# np001.net
KiCad netlist of a schematic drawn in Altium Designer
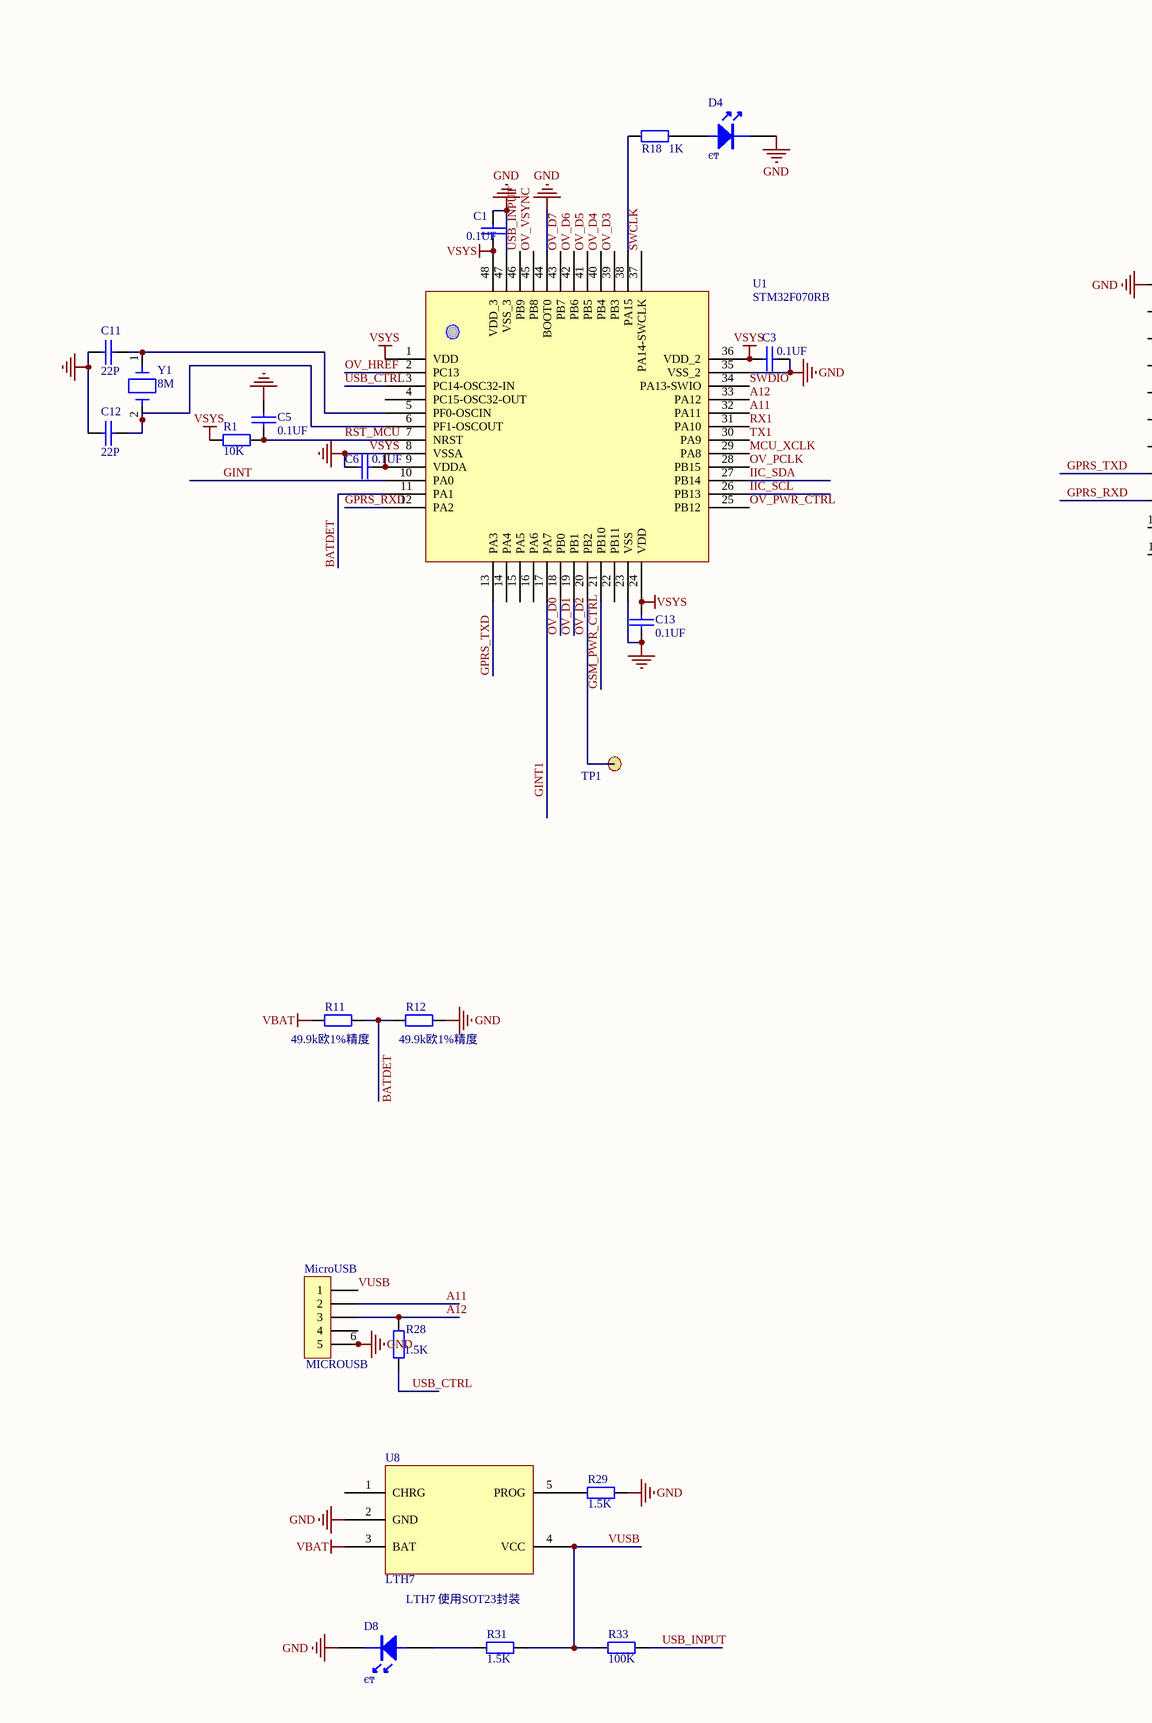
[diagram p0: np001.schdoc, left]
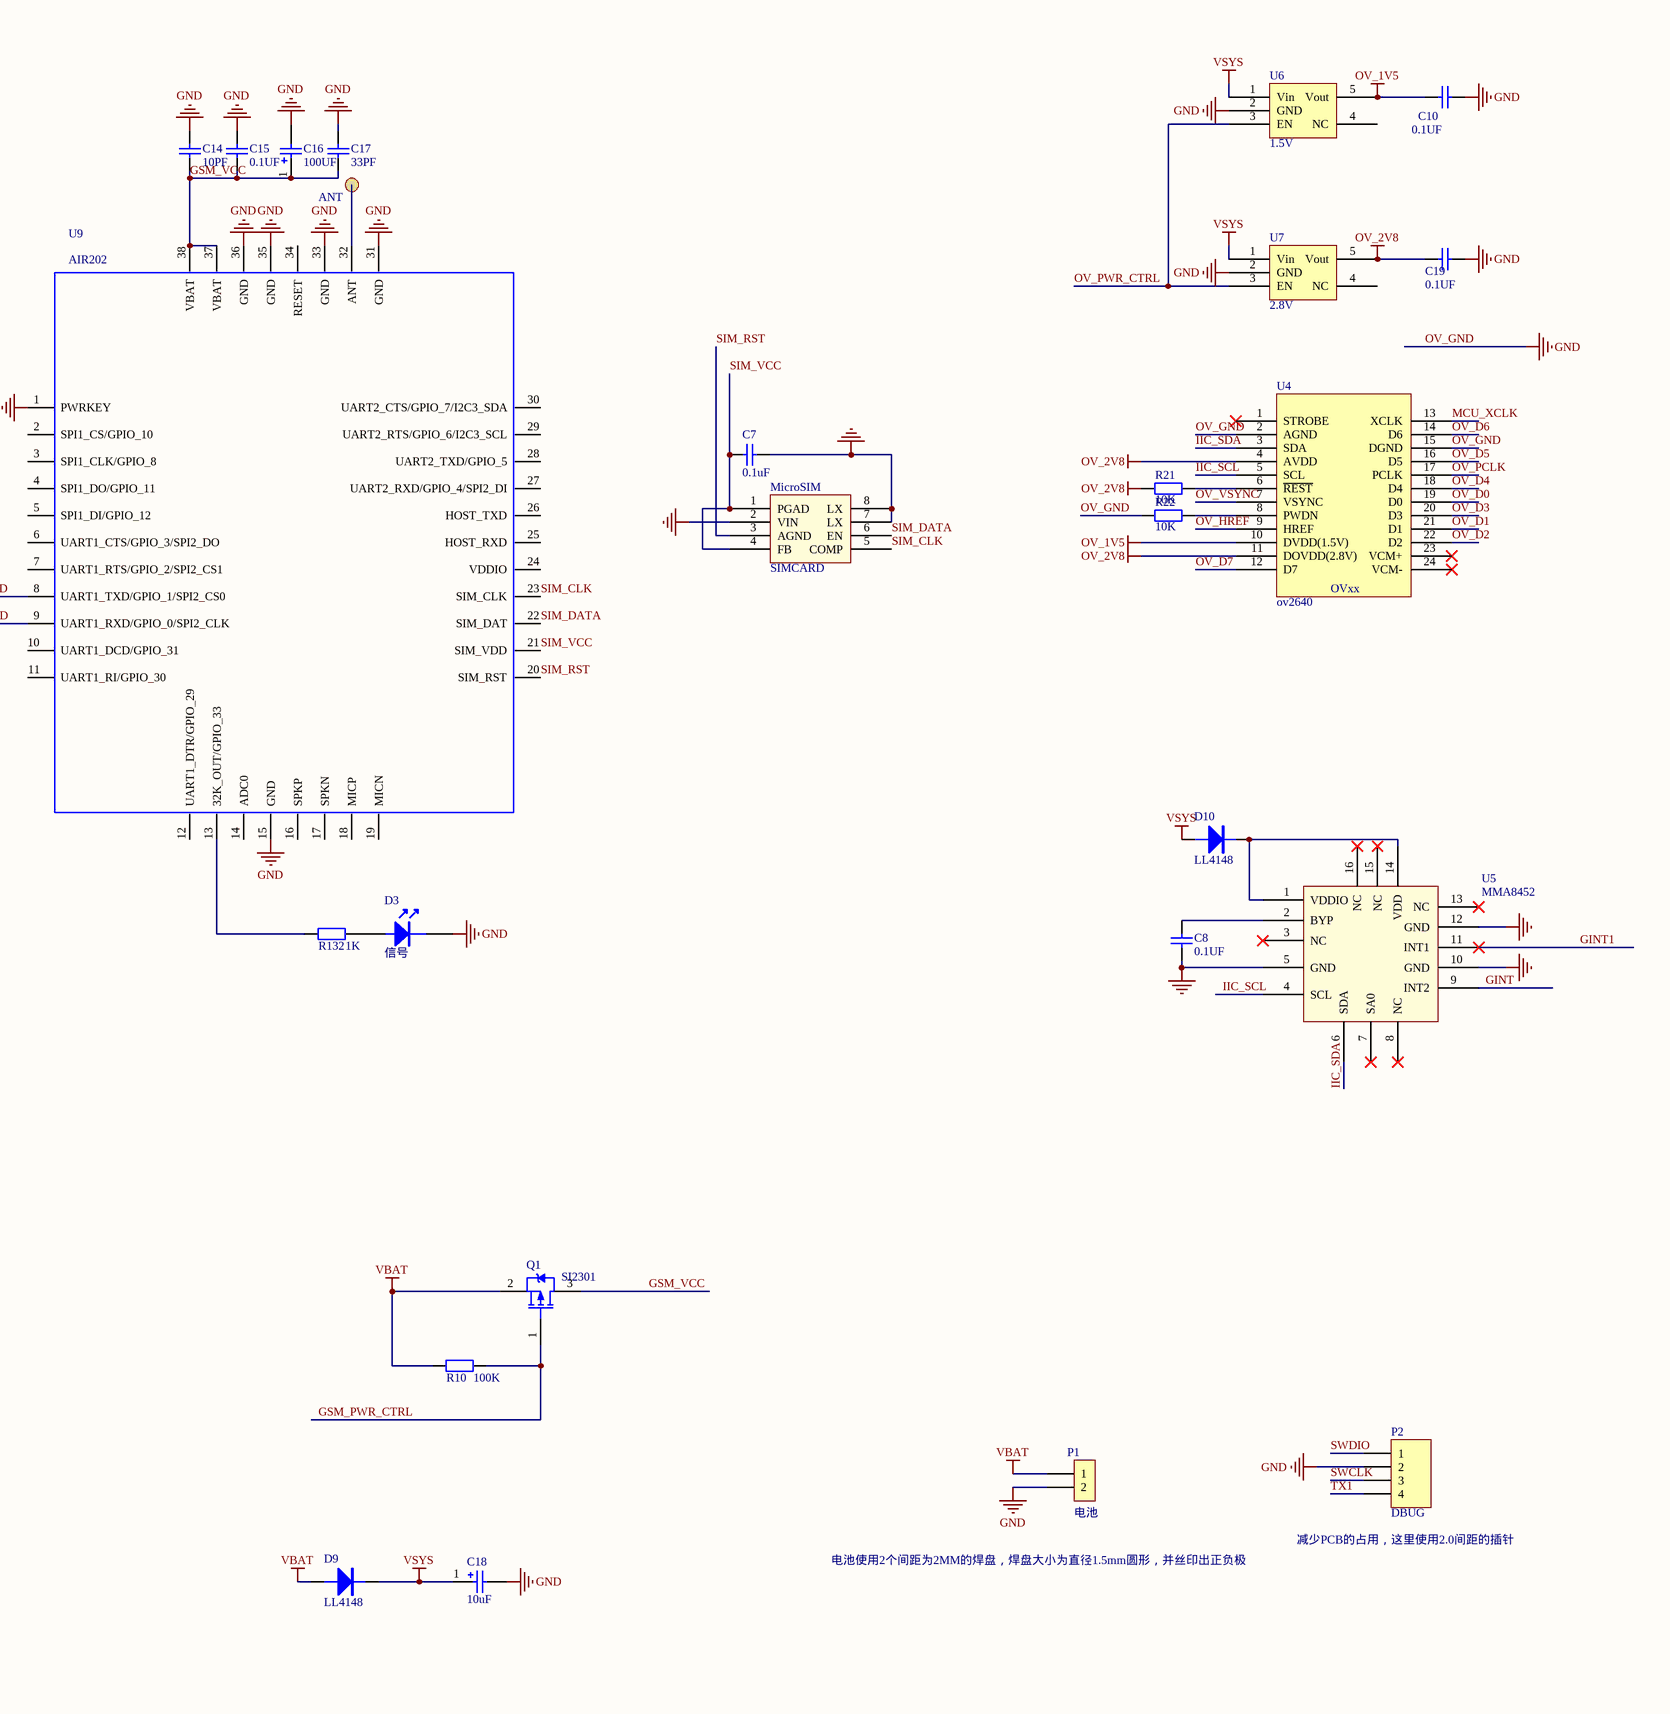
[diagram p1: np001.schdoc, right]

(export (version "E")
  (design (tool "Eeschema 10.0.6"))
  (components
    (comp (ref "ANT") (value "TP") (footprint "CON1") (libsource (lib "HARRIG_Schlib") (part "TP")))
    (comp (ref "C1")
      (value "0.1UF")
      (footprint "0603")
      (description "Capacitor")
      (libsource (lib "*") (part "CAP"))
    )
    (comp (ref "C3")
      (value "0.1UF")
      (footprint "0603")
      (description "Capacitor")
      (libsource (lib "*") (part "CAP"))
    )
    (comp (ref "C5")
      (value "0.1UF")
      (footprint "0603")
      (description "Capacitor")
      (libsource (lib "*") (part "CAP"))
    )
    (comp (ref "C6")
      (value "0.1UF")
      (footprint "0603")
      (description "Capacitor")
      (libsource (lib "*") (part "CAP"))
    )
    (comp (ref "C7")
      (value "0.1uF")
      (footprint "C0603")
      (description "Capacitor")
      (fields (field (name "PUBLISHER") "Altium Limited"))
      (libsource (lib "Miscellaneous Devices") (part "Cap"))
    )
    (comp (ref "C8") (value "0.1UF") (footprint "0603") (libsource (lib "My lib") (part "Cap")))
    (comp (ref "C10") (value "0.1UF") (footprint "0603") (libsource (lib "我的集成库") (part "CAP")))
    (comp (ref "C11")
      (value "22P")
      (footprint "0603")
      (description "Capacitor")
      (libsource (lib "*") (part "CAP"))
    )
    (comp (ref "C12")
      (value "22P")
      (footprint "0603")
      (description "Capacitor")
      (libsource (lib "*") (part "CAP"))
    )
    (comp (ref "C13")
      (value "0.1UF")
      (footprint "0603")
      (description "Capacitor")
      (libsource (lib "*") (part "CAP"))
    )
    (comp (ref "C14") (value "10PF") (footprint "0603") (libsource (lib "我的集成库") (part "CAP")))
    (comp (ref "C15") (value "0.1UF") (footprint "0603") (libsource (lib "我的集成库") (part "CAP")))
    (comp (ref "C16") (value "100UF") (footprint "C7343") (libsource (lib "My lib") (part "Cap_+")))
    (comp (ref "C17") (value "33PF") (footprint "0603") (libsource (lib "我的集成库") (part "CAP")))
    (comp (ref "C18") (value "10uF") (footprint "C3216_10V") (libsource (lib "My lib") (part "Cap_+")))
    (comp (ref "C19") (value "0.1UF") (footprint "0603") (libsource (lib "我的集成库") (part "CAP")))
    (comp (ref "D3") (value "信号") (footprint "LED0603") (libsource (lib "TC35_1") (part "LED")))
    (comp (ref "D4") (value "系统") (footprint "LED0603") (libsource (lib "TC35_1") (part "LED")))
    (comp (ref "D8") (value "系统") (footprint "LED0603") (libsource (lib "TC35_1") (part "LED")))
    (comp (ref "D9") (value "LL4148") (footprint "D1206") (libsource (lib "HZ_LIB") (part "DIODE")))
    (comp (ref "D10") (value "LL4148") (footprint "D1206") (libsource (lib "HZ_LIB") (part "DIODE")))
    (comp (ref "MicroSIM")
      (value "SIMCARD")
      (footprint "PCBComponent_1 - duplicate1")
      (libsource (lib "ARM-ESP8266") (part "aoz1073"))
    )
    (comp (ref "MicroUSB")
      (value "MICROUSB")
      (footprint "mircousb")
      (description "Connector")
      (libsource (lib "sch") (part "CON5"))
    )
    (comp (ref "P1") (value "电池") (footprint "HDR1X2") (libsource (lib "My lib") (part "Header_2")))
    (comp (ref "P2")
      (value "DBUG")
      (footprint "HDR1X4-2.0B")
      (description "Header, 4-Pin, Right Angle")
      (fields (field (name "PUBLISHER") "Altium Limited"))
      (libsource (lib "Miscellaneous Connectors") (part "Header 4H"))
    )
    (comp (ref "Q1")
      (value "SI2301")
      (footprint "SOT-23")
      (description "P-Channel Power MOSFET")
      (fields (field (name "PUBLISHER") "Altium Limited"))
      (libsource (lib "Miscellaneous Devices") (part "PMOS-2"))
    )
    (comp (ref "R1")
      (value "10K")
      (footprint "0603")
      (description "Resistor")
      (fields (field (name "PUBLISHER") "*"))
      (libsource (lib "TC35_1") (part "Res2"))
    )
    (comp (ref "R10")
      (value "100K")
      (footprint "0603")
      (description "Resistor")
      (fields (field (name "PUBLISHER") "*"))
      (libsource (lib "TC35_1") (part "Res2"))
    )
    (comp (ref "R11")
      (value "49.9k欧1%精度")
      (footprint "0603")
      (description "Resistor")
      (fields (field (name "PUBLISHER") "*"))
      (libsource (lib "TC35_1") (part "Res2"))
    )
    (comp (ref "R12")
      (value "49.9k欧1%精度")
      (footprint "0603")
      (description "Resistor")
      (fields (field (name "PUBLISHER") "*"))
      (libsource (lib "TC35_1") (part "Res2"))
    )
    (comp (ref "R18")
      (value "1K")
      (footprint "0603")
      (description "Resistor")
      (fields (field (name "PUBLISHER") "*"))
      (libsource (lib "TC35_1") (part "Res2"))
    )
    (comp (ref "R21")
      (value "10K")
      (footprint "0603")
      (description "Resistor")
      (fields (field (name "PUBLISHER") "*"))
      (libsource (lib "") (part "Res2_1"))
    )
    (comp (ref "R22")
      (value "10K")
      (footprint "0603")
      (description "Resistor")
      (fields (field (name "PUBLISHER") "*"))
      (libsource (lib "") (part "Res2_1"))
    )
    (comp (ref "R28") (value "1.5K") (footprint "0603") (libsource (lib "My lib") (part "Res_SMT")))
    (comp (ref "R29") (value "1.5K") (footprint "0603") (libsource (lib "") (part "Res_SMT_1")))
    (comp (ref "R31") (value "1.5K") (footprint "0603") (libsource (lib "") (part "Res_SMT_2")))
    (comp (ref "R33")
      (value "100K")
      (footprint "0603")
      (description "Resistor")
      (fields (field (name "PUBLISHER") "*"))
      (libsource (lib "TC35_1") (part "Res2"))
    )
    (comp (ref "R132")
      (value "1K")
      (footprint "0603")
      (description "Resistor")
      (fields (field (name "PUBLISHER") "*"))
      (libsource (lib "TC35_1") (part "Res2"))
    )
    (comp (ref "TP1") (value "TP") (footprint "CON1") (libsource (lib "HARRIG_Schlib") (part "TP")))
    (comp (ref "U1") (value "STM32F070RB") (footprint "LQFP48") (libsource (lib "xn") (part "STM32070RB")))
    (comp (ref "U4") (value "ov2640") (footprint "OV2640") (libsource (lib "xn") (part "ov2640")))
    (comp (ref "U5") (value "MMA8452") (footprint "LCC16") (libsource (lib "My lib") (part "MMA8452")))
    (comp (ref "U6") (value "1.5V") (footprint "SOT753") (libsource (lib "我的集成库") (part "NCP699_LDO")))
    (comp (ref "U7") (value "2.8V") (footprint "SOT753") (libsource (lib "我的集成库") (part "NCP699_LDO")))
    (comp (ref "U8") (value "LTH7") (footprint "SOT-23-5") (libsource (lib "air200") (part "LTH7")))
    (comp (ref "U9") (value "AIR202") (footprint "A6391_A11") (libsource (lib "Air202") (part "A6391_A11")))
    (comp (ref "Y1") (value "8M") (footprint "CRY_5032_2P") (libsource (lib "*") (part "CRYTAL")))
  )
  (nets
    (net (code "1") (name "/A11") (class "Default")
      (node (ref "MicroUSB") (pin "2") (pinfunction "2_2") (pintype "passive"))
      (node (ref "U1") (pin "32") (pinfunction "PA11_32") (pintype "passive"))
    )
    (net (code "2") (name "/A12") (class "Default")
      (node (ref "MicroUSB") (pin "3") (pinfunction "3_3") (pintype "passive"))
      (node (ref "R28") (pin "1") (pinfunction "1_1") (pintype "passive"))
      (node (ref "U1") (pin "33") (pinfunction "PA12_33") (pintype "passive"))
    )
    (net (code "3") (name "/BATDET") (class "Default")
      (node (ref "R11") (pin "2") (pinfunction "2_2") (pintype "passive"))
      (node (ref "R12") (pin "1") (pinfunction "1_1") (pintype "passive"))
      (node (ref "U1") (pin "11") (pinfunction "PA1_11") (pintype "passive"))
    )
    (net (code "4") (name "/GINT") (class "Default")
      (node (ref "U1") (pin "10") (pinfunction "PA0_10") (pintype "passive"))
      (node (ref "U5") (pin "9") (pinfunction "INT2_9") (pintype "passive"))
    )
    (net (code "5") (name "/GINT1") (class "Default")
      (node (ref "U1") (pin "17") (pinfunction "PA7_17") (pintype "passive"))
      (node (ref "U5") (pin "11") (pinfunction "INT1_11") (pintype "passive"))
    )
    (net (code "6") (name "/GPRS_RXD") (class "Default")
      (node (ref "U1") (pin "12") (pinfunction "PA2_12") (pintype "passive"))
      (node (ref "U9") (pin "9") (pinfunction "UART1_RXD/GPIO_0/SPI2_CLK_9") (pintype "passive"))
    )
    (net (code "7") (name "/GPRS_TXD") (class "Default")
      (node (ref "U1") (pin "13") (pinfunction "PA3_13") (pintype "passive"))
      (node (ref "U9") (pin "8") (pinfunction "UART1_TXD/GPIO_1/SPI2_CS0_8") (pintype "passive"))
    )
    (net (code "8") (name "/GSM_PWR_CTRL") (class "Default")
      (node (ref "Q1") (pin "1") (pinfunction "G_1") (pintype "passive"))
      (node (ref "R10") (pin "2") (pinfunction "2_2") (pintype "passive"))
      (node (ref "U1") (pin "21") (pinfunction "PB10_21") (pintype "passive"))
    )
    (net (code "9") (name "/GSM_VCC") (class "Default")
      (node (ref "C14") (pin "1") (pinfunction "1_1") (pintype "passive"))
      (node (ref "C15") (pin "1") (pinfunction "1_1") (pintype "passive"))
      (node (ref "C16") (pin "1") (pinfunction "P_1") (pintype "passive"))
      (node (ref "C17") (pin "1") (pinfunction "1_1") (pintype "passive"))
      (node (ref "Q1") (pin "3") (pinfunction "D_3") (pintype "passive"))
      (node (ref "U9") (pin "37") (pinfunction "VBAT_37") (pintype "passive"))
      (node (ref "U9") (pin "38") (pinfunction "VBAT_38") (pintype "passive"))
    )
    (net (code "10") (name "/IIC_SCL") (class "Default")
      (node (ref "U1") (pin "26") (pinfunction "PB13_26") (pintype "passive"))
      (node (ref "U4") (pin "5") (pinfunction "SCL_5") (pintype "passive"))
      (node (ref "U5") (pin "4") (pinfunction "SCL_4") (pintype "passive"))
    )
    (net (code "11") (name "/IIC_SDA") (class "Default")
      (node (ref "U1") (pin "27") (pinfunction "PB14_27") (pintype "passive"))
      (node (ref "U4") (pin "3") (pinfunction "SDA_3") (pintype "passive"))
      (node (ref "U5") (pin "6") (pinfunction "SDA_6") (pintype "passive"))
    )
    (net (code "12") (name "/MCU_XCLK") (class "Default")
      (node (ref "U1") (pin "29") (pinfunction "PA8_29") (pintype "passive"))
      (node (ref "U4") (pin "13") (pinfunction "XCLK_13") (pintype "passive"))
    )
    (net (code "13") (name "/OV_D0") (class "Default")
      (node (ref "U1") (pin "18") (pinfunction "PB0_18") (pintype "passive"))
      (node (ref "U4") (pin "19") (pinfunction "D0_19") (pintype "passive"))
    )
    (net (code "14") (name "/OV_D1") (class "Default")
      (node (ref "U1") (pin "19") (pinfunction "PB1_19") (pintype "passive"))
      (node (ref "U4") (pin "21") (pinfunction "D1_21") (pintype "passive"))
    )
    (net (code "15") (name "/OV_D2") (class "Default")
      (node (ref "TP1") (pin "1") (pintype "passive"))
      (node (ref "U1") (pin "20") (pinfunction "PB2_20") (pintype "passive"))
      (node (ref "U4") (pin "22") (pinfunction "D2_22") (pintype "passive"))
    )
    (net (code "16") (name "/OV_D3") (class "Default")
      (node (ref "U1") (pin "39") (pinfunction "PB3_39") (pintype "passive"))
      (node (ref "U4") (pin "20") (pinfunction "D3_20") (pintype "passive"))
    )
    (net (code "17") (name "/OV_D4") (class "Default")
      (node (ref "U1") (pin "40") (pinfunction "PB4_40") (pintype "passive"))
      (node (ref "U4") (pin "18") (pinfunction "D4_18") (pintype "passive"))
    )
    (net (code "18") (name "/OV_D5") (class "Default")
      (node (ref "U1") (pin "41") (pinfunction "PB5_41") (pintype "passive"))
      (node (ref "U4") (pin "16") (pinfunction "D5_16") (pintype "passive"))
    )
    (net (code "19") (name "/OV_D6") (class "Default")
      (node (ref "U1") (pin "42") (pinfunction "PB6_42") (pintype "passive"))
      (node (ref "U4") (pin "14") (pinfunction "D6_14") (pintype "passive"))
    )
    (net (code "20") (name "/OV_D7") (class "Default")
      (node (ref "U1") (pin "43") (pinfunction "PB7_43") (pintype "passive"))
      (node (ref "U4") (pin "12") (pinfunction "D7_12") (pintype "passive"))
    )
    (net (code "21") (name "/OV_HREF") (class "Default")
      (node (ref "U1") (pin "2") (pinfunction "PC13_2") (pintype "passive"))
      (node (ref "U4") (pin "9") (pinfunction "HREF_9") (pintype "passive"))
    )
    (net (code "22") (name "/OV_PCLK") (class "Default")
      (node (ref "U1") (pin "28") (pinfunction "PB15_28") (pintype "passive"))
      (node (ref "U4") (pin "17") (pinfunction "PCLK_17") (pintype "passive"))
    )
    (net (code "23") (name "/OV_PWR_CTRL") (class "Default")
      (node (ref "U1") (pin "25") (pinfunction "PB12_25") (pintype "passive"))
      (node (ref "U6") (pin "3") (pinfunction "EN_3") (pintype "passive"))
      (node (ref "U7") (pin "3") (pinfunction "EN_3") (pintype "passive"))
    )
    (net (code "24") (name "/OV_VSYNC") (class "Default")
      (node (ref "U1") (pin "45") (pinfunction "PB8_45") (pintype "passive"))
      (node (ref "U4") (pin "7") (pinfunction "VSYNC_7") (pintype "passive"))
    )
    (net (code "25") (name "/RST_MCU") (class "Default")
      (node (ref "C5") (pin "1") (pinfunction "1_1") (pintype "passive"))
      (node (ref "R1") (pin "2") (pinfunction "2_2") (pintype "passive"))
      (node (ref "U1") (pin "7") (pinfunction "NRST_7") (pintype "passive"))
    )
    (net (code "26") (name "/RX1") (class "Default")
      (node (ref "U1") (pin "31") (pinfunction "PA10_31") (pintype "passive"))
    )
    (net (code "27") (name "/SIM_CLK") (class "Default")
      (node (ref "MicroSIM") (pin "5") (pinfunction "COMP_5") (pintype "passive"))
      (node (ref "U9") (pin "23") (pinfunction "SIM_CLK_23") (pintype "passive"))
    )
    (net (code "28") (name "/SIM_DATA") (class "Default")
      (node (ref "MicroSIM") (pin "6") (pinfunction "EN_6") (pintype "passive"))
      (node (ref "U9") (pin "22") (pinfunction "SIM_DAT_22") (pintype "passive"))
    )
    (net (code "29") (name "/SIM_RST") (class "Default")
      (node (ref "MicroSIM") (pin "3") (pinfunction "AGND_3") (pintype "passive"))
      (node (ref "U9") (pin "20") (pinfunction "SIM_RST_20") (pintype "passive"))
    )
    (net (code "30") (name "/SIM_VCC") (class "Default")
      (node (ref "C7") (pin "1") (pinfunction "1_1") (pintype "passive"))
      (node (ref "MicroSIM") (pin "1") (pinfunction "PGAD_1") (pintype "passive"))
      (node (ref "MicroSIM") (pin "4") (pinfunction "FB_4") (pintype "passive"))
      (node (ref "U9") (pin "21") (pinfunction "SIM_VDD_21") (pintype "passive"))
    )
    (net (code "31") (name "/SWCLK") (class "Default")
      (node (ref "P2") (pin "3") (pinfunction "3_3") (pintype "passive"))
      (node (ref "U1") (pin "37") (pinfunction "PA14-SWCLK_37") (pintype "passive"))
    )
    (net (code "32") (name "/SWDIO") (class "Default")
      (node (ref "P2") (pin "1") (pinfunction "1_1") (pintype "passive"))
      (node (ref "U1") (pin "34") (pinfunction "PA13-SWIO_34") (pintype "passive"))
    )
    (net (code "33") (name "/TX1") (class "Default")
      (node (ref "P2") (pin "4") (pinfunction "4_4") (pintype "passive"))
      (node (ref "U1") (pin "30") (pinfunction "PA9_30") (pintype "passive"))
    )
    (net (code "34") (name "/USB_CTRL") (class "Default")
      (node (ref "R28") (pin "2") (pinfunction "2_2") (pintype "passive"))
      (node (ref "U1") (pin "3") (pinfunction "PC14-OSC32-IN_3") (pintype "passive"))
    )
    (net (code "35") (name "/USB_INPUT") (class "Default")
      (node (ref "R33") (pin "2") (pinfunction "2_2") (pintype "passive"))
      (node (ref "U1") (pin "46") (pinfunction "PB9_46") (pintype "passive"))
    )
    (net (code "36") (name "/VUSB") (class "Default")
      (node (ref "MicroUSB") (pin "1") (pinfunction "1_1") (pintype "passive"))
      (node (ref "R31") (pin "1") (pinfunction "1_1") (pintype "passive"))
      (node (ref "R33") (pin "1") (pinfunction "1_1") (pintype "passive"))
      (node (ref "U8") (pin "4") (pinfunction "VCC_4") (pintype "passive"))
    )
    (net (code "37") (name "GND") (class "Default")
      (node (ref "C1") (pin "2") (pinfunction "2_2") (pintype "passive"))
      (node (ref "C10") (pin "2") (pinfunction "2_2") (pintype "passive"))
      (node (ref "C11") (pin "2") (pinfunction "2_2") (pintype "passive"))
      (node (ref "C12") (pin "2") (pinfunction "2_2") (pintype "passive"))
      (node (ref "C13") (pin "2") (pinfunction "2_2") (pintype "passive"))
      (node (ref "C14") (pin "2") (pinfunction "2_2") (pintype "passive"))
      (node (ref "C15") (pin "2") (pinfunction "2_2") (pintype "passive"))
      (node (ref "C16") (pin "2") (pinfunction "N_2") (pintype "passive"))
      (node (ref "C17") (pin "2") (pinfunction "2_2") (pintype "passive"))
      (node (ref "C18") (pin "2") (pinfunction "N_2") (pintype "passive"))
      (node (ref "C19") (pin "2") (pinfunction "2_2") (pintype "passive"))
      (node (ref "C3") (pin "2") (pinfunction "2_2") (pintype "passive"))
      (node (ref "C5") (pin "2") (pinfunction "2_2") (pintype "passive"))
      (node (ref "C6") (pin "1") (pinfunction "1_1") (pintype "passive"))
      (node (ref "C7") (pin "2") (pinfunction "2_2") (pintype "passive"))
      (node (ref "C8") (pin "1") (pinfunction "1_1") (pintype "passive"))
      (node (ref "D3") (pin "2") (pinfunction "2_2") (pintype "passive"))
      (node (ref "D4") (pin "2") (pinfunction "2_2") (pintype "passive"))
      (node (ref "D8") (pin "2") (pinfunction "2_2") (pintype "passive"))
      (node (ref "MicroSIM") (pin "2") (pinfunction "VIN_2") (pintype "passive"))
      (node (ref "MicroSIM") (pin "7") (pinfunction "LX_7") (pintype "passive"))
      (node (ref "MicroSIM") (pin "8") (pinfunction "LX_8") (pintype "passive"))
      (node (ref "MicroUSB") (pin "5") (pinfunction "5_5") (pintype "passive"))
      (node (ref "MicroUSB") (pin "6") (pintype "passive"))
      (node (ref "P1") (pin "2") (pinfunction "2_2") (pintype "passive"))
      (node (ref "P2") (pin "2") (pinfunction "2_2") (pintype "passive"))
      (node (ref "R12") (pin "2") (pinfunction "2_2") (pintype "passive"))
      (node (ref "R22") (pin "2") (pinfunction "2_2") (pintype "passive"))
      (node (ref "R29") (pin "2") (pinfunction "2_2") (pintype "passive"))
      (node (ref "U1") (pin "23") (pinfunction "VSS_23") (pintype "passive"))
      (node (ref "U1") (pin "35") (pinfunction "VSS_2_35") (pintype "passive"))
      (node (ref "U1") (pin "44") (pinfunction "BOOT0_44") (pintype "passive"))
      (node (ref "U1") (pin "47") (pinfunction "VSS_3_47") (pintype "passive"))
      (node (ref "U1") (pin "8") (pinfunction "VSSA_8") (pintype "passive"))
      (node (ref "U4") (pin "15") (pinfunction "DGND_15") (pintype "passive"))
      (node (ref "U4") (pin "2") (pinfunction "AGND_2") (pintype "passive"))
      (node (ref "U5") (pin "10") (pinfunction "GND_10") (pintype "passive"))
      (node (ref "U5") (pin "12") (pinfunction "GND_12") (pintype "passive"))
      (node (ref "U5") (pin "5") (pinfunction "GND_5") (pintype "passive"))
      (node (ref "U6") (pin "2") (pinfunction "GND_2") (pintype "passive"))
      (node (ref "U7") (pin "2") (pinfunction "GND_2") (pintype "passive"))
      (node (ref "U8") (pin "2") (pinfunction "GND_2") (pintype "passive"))
      (node (ref "U9") (pin "1") (pinfunction "PWRKEY_1") (pintype "passive"))
      (node (ref "U9") (pin "15") (pinfunction "GND_15") (pintype "passive"))
      (node (ref "U9") (pin "31") (pinfunction "GND_31") (pintype "passive"))
      (node (ref "U9") (pin "33") (pinfunction "GND_33") (pintype "passive"))
      (node (ref "U9") (pin "35") (pinfunction "GND_35") (pintype "passive"))
      (node (ref "U9") (pin "36") (pinfunction "GND_36") (pintype "passive"))
      (node (ref "U9") (pin "39") (pinfunction "GND_39") (pintype "power_in"))
      (node (ref "U9") (pin "40") (pinfunction "GND_40") (pintype "power_in"))
      (node (ref "U9") (pin "41") (pinfunction "GND_41") (pintype "power_in"))
    )
    (net (code "38") (name "Net-(D3-Pad1)") (class "Default")
      (node (ref "D3") (pin "1") (pinfunction "1_1") (pintype "passive"))
      (node (ref "R132") (pin "2") (pinfunction "2_2") (pintype "passive"))
    )
    (net (code "39") (name "Net-(D4-Pad1)") (class "Default")
      (node (ref "D4") (pin "1") (pinfunction "1_1") (pintype "passive"))
      (node (ref "R18") (pin "2") (pinfunction "2_2") (pintype "passive"))
    )
    (net (code "40") (name "Net-(D8-Pad1)") (class "Default")
      (node (ref "D8") (pin "1") (pinfunction "1_1") (pintype "passive"))
      (node (ref "R31") (pin "2") (pinfunction "2_2") (pintype "passive"))
    )
    (net (code "41") (name "Net-(D10-K)") (class "Default")
      (node (ref "D10") (pin "2") (pinfunction "K_2") (pintype "passive"))
      (node (ref "U5") (pin "1") (pinfunction "VDDIO_1") (pintype "passive"))
      (node (ref "U5") (pin "14") (pinfunction "VDD_14") (pintype "passive"))
    )
    (net (code "42") (name "Net-(U1-PA15)") (class "Default")
      (node (ref "R18") (pin "1") (pinfunction "1_1") (pintype "passive"))
      (node (ref "U1") (pin "38") (pinfunction "PA15_38") (pintype "passive"))
    )
    (net (code "43") (name "Net-(U1-PF0-OSCIN)") (class "Default")
      (node (ref "C11") (pin "1") (pinfunction "1_1") (pintype "passive"))
      (node (ref "U1") (pin "5") (pinfunction "PF0-OSCIN_5") (pintype "passive"))
      (node (ref "Y1") (pin "1") (pinfunction "1_1") (pintype "passive"))
    )
    (net (code "44") (name "Net-(U1-PF1-OSCOUT)") (class "Default")
      (node (ref "C12") (pin "1") (pinfunction "1_1") (pintype "passive"))
      (node (ref "U1") (pin "6") (pinfunction "PF1-OSCOUT_6") (pintype "passive"))
      (node (ref "Y1") (pin "2") (pinfunction "2_2") (pintype "passive"))
    )
    (net (code "45") (name "Net-(U4-PWDN)") (class "Default")
      (node (ref "R22") (pin "1") (pinfunction "1_1") (pintype "passive"))
      (node (ref "U4") (pin "8") (pinfunction "PWDN_8") (pintype "passive"))
    )
    (net (code "46") (name "Net-(U4-~{REST})") (class "Default")
      (node (ref "R21") (pin "1") (pinfunction "1_1") (pintype "passive"))
      (node (ref "U4") (pin "6") (pinfunction "~{REST}_6") (pintype "passive"))
    )
    (net (code "47") (name "Net-(U5-BYP)") (class "Default")
      (node (ref "C8") (pin "2") (pinfunction "2_2") (pintype "passive"))
      (node (ref "U5") (pin "2") (pinfunction "BYP_2") (pintype "passive"))
    )
    (net (code "48") (name "Net-(U8-PROG)") (class "Default")
      (node (ref "R29") (pin "1") (pinfunction "1_1") (pintype "passive"))
      (node (ref "U8") (pin "5") (pinfunction "PROG_5") (pintype "passive"))
    )
    (net (code "49") (name "Net-(U9-32K_OUT{slash}GPIO_33)") (class "Default")
      (node (ref "R132") (pin "1") (pinfunction "1_1") (pintype "passive"))
      (node (ref "U9") (pin "13") (pinfunction "32K_OUT/GPIO_33_13") (pintype "passive"))
    )
    (net (code "50") (name "Net-(U9-ANT)") (class "Default")
      (node (ref "ANT") (pin "1") (pintype "passive"))
      (node (ref "U9") (pin "32") (pinfunction "ANT_32") (pintype "passive"))
    )
    (net (code "51") (name "OV_1V5") (class "Default")
      (node (ref "C10") (pin "1") (pinfunction "1_1") (pintype "passive"))
      (node (ref "U4") (pin "10") (pinfunction "DVDD(1.5V)_10") (pintype "passive"))
      (node (ref "U6") (pin "5") (pinfunction "Vout_5") (pintype "passive"))
    )
    (net (code "52") (name "OV_2V8") (class "Default")
      (node (ref "C19") (pin "1") (pinfunction "1_1") (pintype "passive"))
      (node (ref "R21") (pin "2") (pinfunction "2_2") (pintype "passive"))
      (node (ref "U4") (pin "11") (pinfunction "DOVDD(2.8V)_11") (pintype "passive"))
      (node (ref "U4") (pin "4") (pinfunction "AVDD_4") (pintype "passive"))
      (node (ref "U7") (pin "5") (pinfunction "Vout_5") (pintype "passive"))
    )
    (net (code "53") (name "VBAT") (class "Default")
      (node (ref "D9") (pin "1") (pinfunction "A_1") (pintype "passive"))
      (node (ref "P1") (pin "1") (pinfunction "1_1") (pintype "passive"))
      (node (ref "Q1") (pin "2") (pinfunction "S_2") (pintype "passive"))
      (node (ref "R10") (pin "1") (pinfunction "1_1") (pintype "passive"))
      (node (ref "R11") (pin "1") (pinfunction "1_1") (pintype "passive"))
      (node (ref "U8") (pin "3") (pinfunction "BAT_3") (pintype "passive"))
    )
    (net (code "54") (name "VSYS") (class "Default")
      (node (ref "C1") (pin "1") (pinfunction "1_1") (pintype "passive"))
      (node (ref "C13") (pin "1") (pinfunction "1_1") (pintype "passive"))
      (node (ref "C18") (pin "1") (pinfunction "P_1") (pintype "passive"))
      (node (ref "C3") (pin "1") (pinfunction "1_1") (pintype "passive"))
      (node (ref "C6") (pin "2") (pinfunction "2_2") (pintype "passive"))
      (node (ref "D10") (pin "1") (pinfunction "A_1") (pintype "passive"))
      (node (ref "D9") (pin "2") (pinfunction "K_2") (pintype "passive"))
      (node (ref "R1") (pin "1") (pinfunction "1_1") (pintype "passive"))
      (node (ref "U1") (pin "1") (pinfunction "VDD_1") (pintype "passive"))
      (node (ref "U1") (pin "24") (pinfunction "VDD_24") (pintype "passive"))
      (node (ref "U1") (pin "36") (pinfunction "VDD_2_36") (pintype "passive"))
      (node (ref "U1") (pin "48") (pinfunction "VDD_3_48") (pintype "passive"))
      (node (ref "U1") (pin "9") (pinfunction "VDDA_9") (pintype "passive"))
      (node (ref "U6") (pin "1") (pinfunction "Vin_1") (pintype "passive"))
      (node (ref "U7") (pin "1") (pinfunction "Vin_1") (pintype "passive"))
    )
    (net (code "55") (name "unconnected-(MicroUSB-Pad4)") (class "Default")
      (node (ref "MicroUSB") (pin "4") (pinfunction "4_4") (pintype "passive"))
    )
    (net (code "56") (name "unconnected-(U1-PA4-Pad14)") (class "Default")
      (node (ref "U1") (pin "14") (pinfunction "PA4_14") (pintype "passive"))
    )
    (net (code "57") (name "unconnected-(U1-PA5-Pad15)") (class "Default")
      (node (ref "U1") (pin "15") (pinfunction "PA5_15") (pintype "passive"))
    )
    (net (code "58") (name "unconnected-(U1-PA6-Pad16)") (class "Default")
      (node (ref "U1") (pin "16") (pinfunction "PA6_16") (pintype "passive"))
    )
    (net (code "59") (name "unconnected-(U1-PB11-Pad22)") (class "Default")
      (node (ref "U1") (pin "22") (pinfunction "PB11_22") (pintype "passive"))
    )
    (net (code "60") (name "unconnected-(U1-PC15-OSC32-OUT-Pad4)") (class "Default")
      (node (ref "U1") (pin "4") (pinfunction "PC15-OSC32-OUT_4") (pintype "passive"))
    )
    (net (code "61") (name "unconnected-(U4-STROBE-Pad1)") (class "Default")
      (node (ref "U4") (pin "1") (pinfunction "STROBE_1") (pintype "passive+no_connect"))
    )
    (net (code "62") (name "unconnected-(U4-VCM+-Pad23)") (class "Default")
      (node (ref "U4") (pin "23") (pinfunction "VCM+_23") (pintype "passive+no_connect"))
    )
    (net (code "63") (name "unconnected-(U4-VCM--Pad24)") (class "Default")
      (node (ref "U4") (pin "24") (pinfunction "VCM-_24") (pintype "passive+no_connect"))
    )
    (net (code "64") (name "unconnected-(U5-NC-Pad3)") (class "Default")
      (node (ref "U5") (pin "3") (pinfunction "NC_3") (pintype "passive+no_connect"))
    )
    (net (code "65") (name "unconnected-(U5-NC-Pad8)") (class "Default")
      (node (ref "U5") (pin "8") (pinfunction "NC_8") (pintype "passive+no_connect"))
    )
    (net (code "66") (name "unconnected-(U5-NC-Pad13)") (class "Default")
      (node (ref "U5") (pin "13") (pinfunction "NC_13") (pintype "passive+no_connect"))
    )
    (net (code "67") (name "unconnected-(U5-NC-Pad15)") (class "Default")
      (node (ref "U5") (pin "15") (pinfunction "NC_15") (pintype "passive+no_connect"))
    )
    (net (code "68") (name "unconnected-(U5-NC-Pad16)") (class "Default")
      (node (ref "U5") (pin "16") (pinfunction "NC_16") (pintype "passive+no_connect"))
    )
    (net (code "69") (name "unconnected-(U5-SA0-Pad7)") (class "Default")
      (node (ref "U5") (pin "7") (pinfunction "SA0_7") (pintype "passive+no_connect"))
    )
    (net (code "70") (name "unconnected-(U6-NC-Pad4)") (class "Default")
      (node (ref "U6") (pin "4") (pinfunction "NC_4") (pintype "passive"))
    )
    (net (code "71") (name "unconnected-(U7-NC-Pad4)") (class "Default")
      (node (ref "U7") (pin "4") (pinfunction "NC_4") (pintype "passive"))
    )
    (net (code "72") (name "unconnected-(U8-CHRG-Pad1)") (class "Default")
      (node (ref "U8") (pin "1") (pinfunction "CHRG_1") (pintype "passive"))
    )
    (net (code "73") (name "unconnected-(U9-ADC0-Pad14)") (class "Default")
      (node (ref "U9") (pin "14") (pinfunction "ADC0_14") (pintype "passive"))
    )
    (net (code "74") (name "unconnected-(U9-HOST_RXD-Pad25)") (class "Default")
      (node (ref "U9") (pin "25") (pinfunction "HOST_RXD_25") (pintype "passive"))
    )
    (net (code "75") (name "unconnected-(U9-HOST_TXD-Pad26)") (class "Default")
      (node (ref "U9") (pin "26") (pinfunction "HOST_TXD_26") (pintype "passive"))
    )
    (net (code "76") (name "unconnected-(U9-MICN-Pad19)") (class "Default")
      (node (ref "U9") (pin "19") (pinfunction "MICN_19") (pintype "passive"))
    )
    (net (code "77") (name "unconnected-(U9-MICP-Pad18)") (class "Default")
      (node (ref "U9") (pin "18") (pinfunction "MICP_18") (pintype "passive"))
    )
    (net (code "78") (name "unconnected-(U9-RESET-Pad34)") (class "Default")
      (node (ref "U9") (pin "34") (pinfunction "RESET_34") (pintype "passive"))
    )
    (net (code "79") (name "unconnected-(U9-SPI1_CLK{slash}GPIO_8-Pad3)") (class "Default")
      (node (ref "U9") (pin "3") (pinfunction "SPI1_CLK/GPIO_8_3") (pintype "passive"))
    )
    (net (code "80") (name "unconnected-(U9-SPI1_CS{slash}GPIO_10-Pad2)") (class "Default")
      (node (ref "U9") (pin "2") (pinfunction "SPI1_CS/GPIO_10_2") (pintype "passive"))
    )
    (net (code "81") (name "unconnected-(U9-SPI1_DI{slash}GPIO_12-Pad5)") (class "Default")
      (node (ref "U9") (pin "5") (pinfunction "SPI1_DI/GPIO_12_5") (pintype "passive"))
    )
    (net (code "82") (name "unconnected-(U9-SPI1_DO{slash}GPIO_11-Pad4)") (class "Default")
      (node (ref "U9") (pin "4") (pinfunction "SPI1_DO/GPIO_11_4") (pintype "passive"))
    )
    (net (code "83") (name "unconnected-(U9-SPKN-Pad17)") (class "Default")
      (node (ref "U9") (pin "17") (pinfunction "SPKN_17") (pintype "passive"))
    )
    (net (code "84") (name "unconnected-(U9-SPKP-Pad16)") (class "Default")
      (node (ref "U9") (pin "16") (pinfunction "SPKP_16") (pintype "passive"))
    )
    (net (code "85") (name "unconnected-(U9-UART1_CTS{slash}GPIO_3{slash}SPI2_DO-Pad6)") (class "Default")
      (node (ref "U9") (pin "6") (pinfunction "UART1_CTS/GPIO_3/SPI2_DO_6") (pintype "passive"))
    )
    (net (code "86") (name "unconnected-(U9-UART1_DCD{slash}GPIO_31-Pad10)") (class "Default")
      (node (ref "U9") (pin "10") (pinfunction "UART1_DCD/GPIO_31_10") (pintype "passive"))
    )
    (net (code "87") (name "unconnected-(U9-UART1_DTR{slash}GPIO_29-Pad12)") (class "Default")
      (node (ref "U9") (pin "12") (pinfunction "UART1_DTR/GPIO_29_12") (pintype "passive"))
    )
    (net (code "88") (name "unconnected-(U9-UART1_RI{slash}GPIO_30-Pad11)") (class "Default")
      (node (ref "U9") (pin "11") (pinfunction "UART1_RI/GPIO_30_11") (pintype "passive"))
    )
    (net (code "89") (name "unconnected-(U9-UART1_RTS{slash}GPIO_2{slash}SPI2_CS1-Pad7)") (class "Default")
      (node (ref "U9") (pin "7") (pinfunction "UART1_RTS/GPIO_2/SPI2_CS1_7") (pintype "passive"))
    )
    (net (code "90") (name "unconnected-(U9-UART2_CTS{slash}GPIO_7{slash}I2C3_SDA-Pad30)") (class "Default")
      (node (ref "U9") (pin "30") (pinfunction "UART2_CTS/GPIO_7/I2C3_SDA_30") (pintype "passive"))
    )
    (net (code "91") (name "unconnected-(U9-UART2_RTS{slash}GPIO_6{slash}I2C3_SCL-Pad29)") (class "Default")
      (node (ref "U9") (pin "29") (pinfunction "UART2_RTS/GPIO_6/I2C3_SCL_29") (pintype "passive"))
    )
    (net (code "92") (name "unconnected-(U9-UART2_RXD{slash}GPIO_4{slash}SPI2_DI-Pad27)") (class "Default")
      (node (ref "U9") (pin "27") (pinfunction "UART2_RXD/GPIO_4/SPI2_DI_27") (pintype "passive"))
    )
    (net (code "93") (name "unconnected-(U9-UART2_TXD{slash}GPIO_5-Pad28)") (class "Default")
      (node (ref "U9") (pin "28") (pinfunction "UART2_TXD/GPIO_5_28") (pintype "passive"))
    )
    (net (code "94") (name "unconnected-(U9-VDDIO-Pad24)") (class "Default")
      (node (ref "U9") (pin "24") (pinfunction "VDDIO_24") (pintype "passive"))
    )
  )
)
